# design.net
KiCad netlist of a schematic drawn in EasyEDA Pro
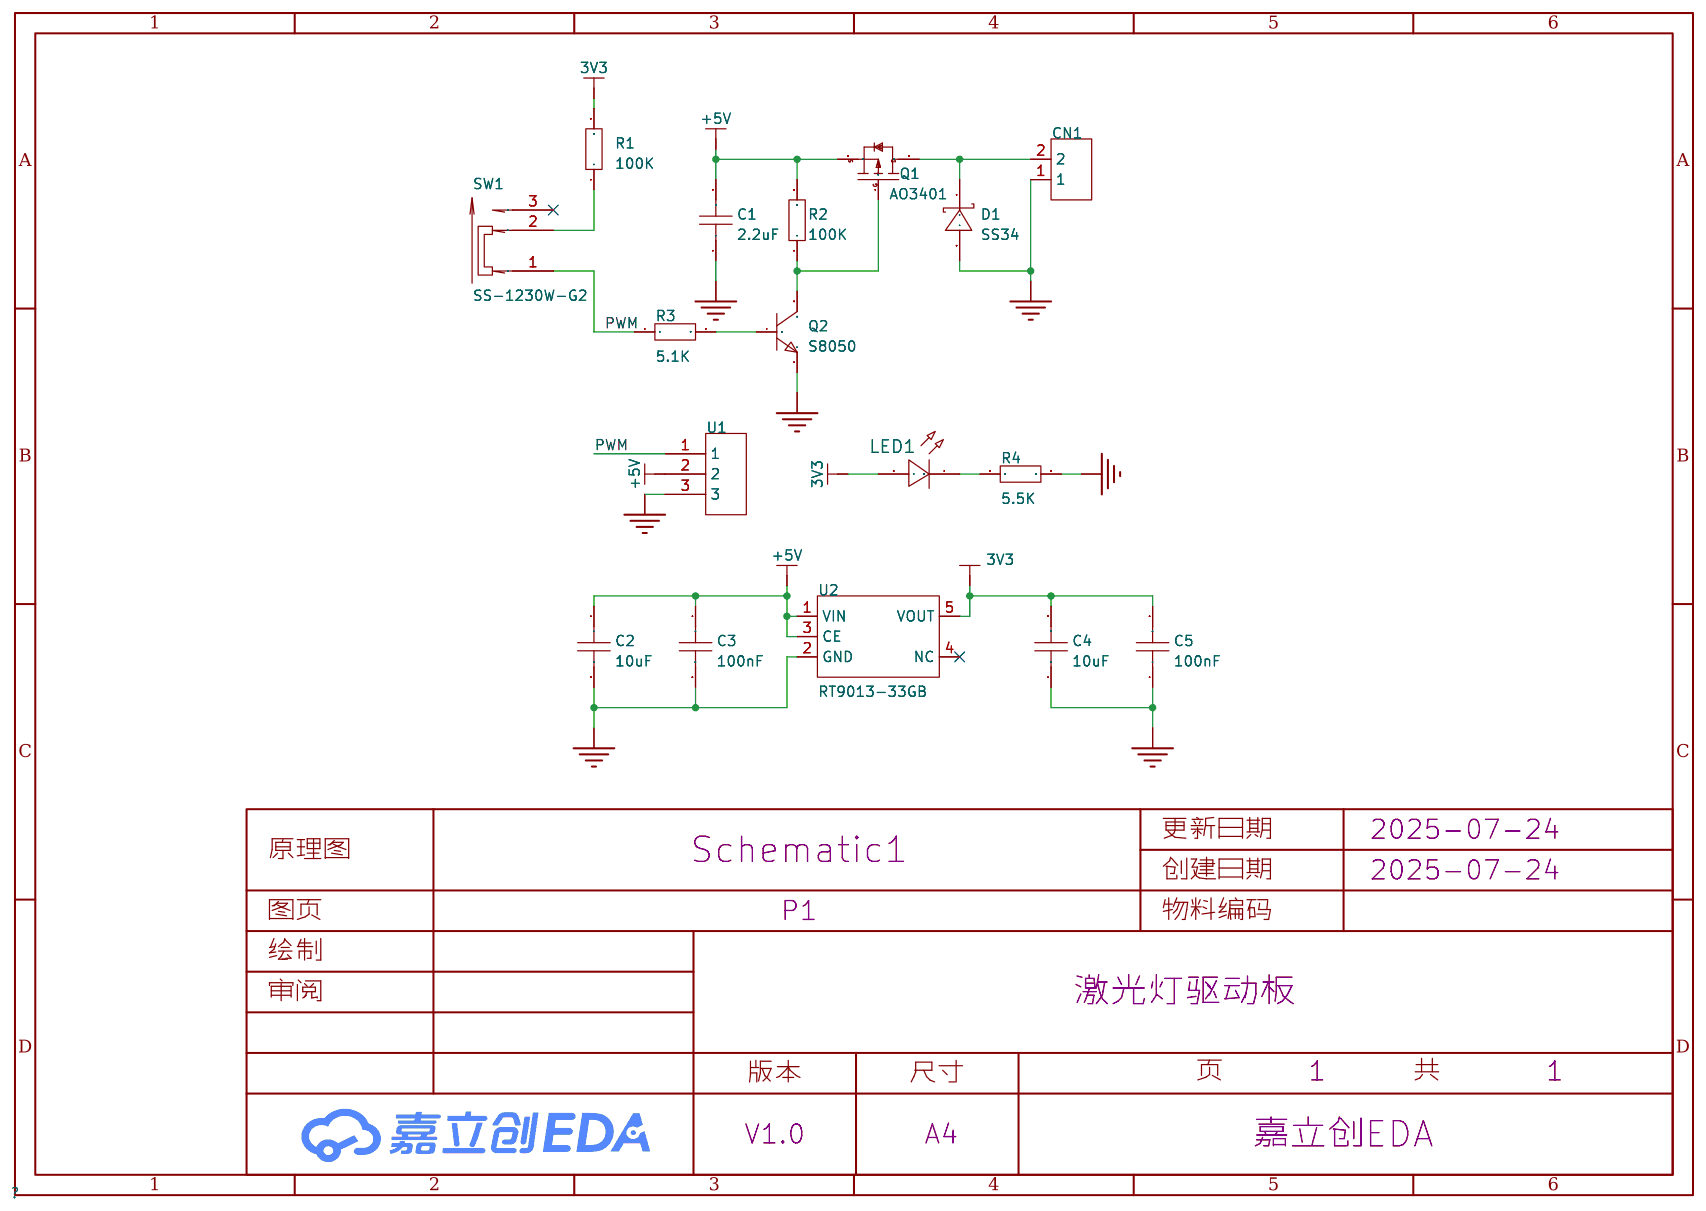
[diagram p0: schematic sheet]

(export (version "E")
  (design (tool "Eeschema 10.0.6"))
  (components
    (comp (ref "C1")
      (value "2.2uF")
      (footprint "easyedapro:C0603")
      (libsource (lib "easyedapro") (part "CapAcitance"))
    )
    (comp (ref "C2")
      (value "10uF")
      (footprint "easyedapro:C0603")
      (libsource (lib "easyedapro") (part "CapAcitance"))
    )
    (comp (ref "C3")
      (value "100nF")
      (footprint "easyedapro:C0603")
      (libsource (lib "easyedapro") (part "CapAcitance"))
    )
    (comp (ref "C4")
      (value "10uF")
      (footprint "easyedapro:C0603")
      (libsource (lib "easyedapro") (part "CapAcitance"))
    )
    (comp (ref "C5")
      (value "100nF")
      (footprint "easyedapro:C0603")
      (libsource (lib "easyedapro") (part "CapAcitance"))
    )
    (comp (ref "CN1")
      (value "XH2.54-2PIN-直针")
      (footprint "easyedapro:CONN-TH_XH2.54-2P")
      (libsource (lib "easyedapro") (part "XH2.54-2PIN-直针"))
    )
    (comp (ref "D1")
      (value "SS34")
      (footprint "easyedapro:SMA_L4.3-W2.6-LS5.0-RD")
      (libsource (lib "easyedapro") (part "SS34_C9900023345"))
    )
    (comp (ref "LED1")
      (value "~")
      (footprint "easyedapro:LED_0603")
      (libsource (lib "easyedapro") (part "LED_R"))
    )
    (comp (ref "Q1")
      (value "AO3401")
      (footprint "easyedapro:SOT-23-3_L2.9-W1.6-P1.90-LS2.8-BR")
      (libsource (lib "easyedapro") (part "AO3401_C9900008520"))
    )
    (comp (ref "Q2")
      (value "S8050")
      (footprint "easyedapro:SOT-23-3_L2.9-W1.3-P1.90-LS2.4-BR")
      (description "NPN 25V 500mA 120-400 SOT-23")
      (fields (field (name "Manufacturer") "Doeshare(德芯)"))
      (libsource (lib "easyedapro") (part "S8050_C2931719"))
    )
    (comp (ref "R1") (value "100K") (footprint "easyedapro:R0603") (libsource (lib "easyedapro") (part "电阻")))
    (comp (ref "R2") (value "100K") (footprint "easyedapro:R0603") (libsource (lib "easyedapro") (part "电阻")))
    (comp (ref "R3") (value "5.1K") (footprint "easyedapro:R0603") (libsource (lib "easyedapro") (part "电阻")))
    (comp (ref "R4") (value "5.5K") (footprint "easyedapro:R0603") (libsource (lib "easyedapro") (part "电阻")))
    (comp (ref "SW1")
      (value "SS-1230W-G2")
      (footprint "easyedapro:SW-SMD_SS-1230W-G2")
      (fields (field (name "Manufacturer") "RISHENG(日昇)"))
      (libsource (lib "easyedapro") (part "SS-1230W-G2"))
    )
    (comp (ref "U1")
      (value "~")
      (footprint "easyedapro:X2.54_3p")
      (libsource (lib "easyedapro") (part "X2.54 _3p"))
    )
    (comp (ref "U2")
      (value "RT9013-33GB")
      (footprint "easyedapro:SOT-23-5_L2.9-W1.6-P0.95-LS2.8-BR")
      (description "输出类型:固定;工作电压:7V;输出电压:3.3V;输出电流:500mA;电源纹波抑制比(PSRR):-;输出极性:正极;")
      (fields (field (name "Manufacturer") "TECH PUBLIC(台舟)"))
      (libsource (lib "easyedapro") (part "RT9013-33GB_C19268157"))
    )
  )
  (nets
    (net (code "1") (name "+5V") (class "Default")
      (node (ref "C1") (pin "2") (pinfunction "2_2") (pintype "input"))
      (node (ref "C2") (pin "1") (pinfunction "1_1") (pintype "input"))
      (node (ref "C3") (pin "1") (pinfunction "1_1") (pintype "input"))
      (node (ref "Q1") (pin "2") (pinfunction "S_2") (pintype "unspecified"))
      (node (ref "R2") (pin "2") (pinfunction "2_2") (pintype "input"))
      (node (ref "U1") (pin "2") (pinfunction "2_2") (pintype "input"))
      (node (ref "U2") (pin "1") (pinfunction "VIN_1") (pintype "unspecified"))
      (node (ref "U2") (pin "3") (pinfunction "CE_3") (pintype "unspecified"))
    )
    (net (code "2") (name "/PWM") (class "Default")
      (node (ref "R3") (pin "1") (pinfunction "1_1") (pintype "input"))
      (node (ref "SW1") (pin "1") (pinfunction "1_1") (pintype "unspecified"))
      (node (ref "U1") (pin "1") (pinfunction "1_1") (pintype "input"))
    )
    (net (code "3") (name "3V3") (class "Default")
      (node (ref "C4") (pin "2") (pinfunction "2_2") (pintype "input"))
      (node (ref "C5") (pin "2") (pinfunction "2_2") (pintype "input"))
      (node (ref "LED1") (pin "2") (pinfunction "A_2") (pintype "input"))
      (node (ref "R1") (pin "2") (pinfunction "2_2") (pintype "input"))
      (node (ref "U2") (pin "5") (pinfunction "VOUT_5") (pintype "unspecified"))
    )
    (net (code "4") (name "GND") (class "Default")
      (node (ref "C1") (pin "1") (pinfunction "1_1") (pintype "input"))
      (node (ref "C2") (pin "2") (pinfunction "2_2") (pintype "input"))
      (node (ref "C3") (pin "2") (pinfunction "2_2") (pintype "input"))
      (node (ref "C4") (pin "1") (pinfunction "1_1") (pintype "input"))
      (node (ref "C5") (pin "1") (pinfunction "1_1") (pintype "input"))
      (node (ref "CN1") (pin "1") (pinfunction "1_1") (pintype "unspecified"))
      (node (ref "D1") (pin "2") (pinfunction "A_2") (pintype "unspecified"))
      (node (ref "Q2") (pin "2") (pinfunction "E_2") (pintype "input"))
      (node (ref "R4") (pin "2") (pinfunction "2_2") (pintype "input"))
      (node (ref "U1") (pin "3") (pinfunction "3_3") (pintype "input"))
      (node (ref "U2") (pin "2") (pinfunction "GND_2") (pintype "unspecified"))
    )
    (net (code "5") (name "Net-(D1-K)") (class "Default")
      (node (ref "CN1") (pin "2") (pinfunction "2_2") (pintype "unspecified"))
      (node (ref "D1") (pin "1") (pinfunction "K_1") (pintype "unspecified"))
      (node (ref "Q1") (pin "3") (pinfunction "D_3") (pintype "unspecified"))
    )
    (net (code "6") (name "Net-(LED1-C)") (class "Default")
      (node (ref "LED1") (pin "1") (pinfunction "C_1") (pintype "input"))
      (node (ref "R4") (pin "1") (pinfunction "1_1") (pintype "input"))
    )
    (net (code "7") (name "Net-(Q1-G)") (class "Default")
      (node (ref "Q1") (pin "1") (pinfunction "G_1") (pintype "unspecified"))
      (node (ref "Q2") (pin "3") (pinfunction "C_3") (pintype "input"))
      (node (ref "R2") (pin "1") (pinfunction "1_1") (pintype "input"))
    )
    (net (code "8") (name "Net-(Q2-B)") (class "Default")
      (node (ref "Q2") (pin "1") (pinfunction "B_1") (pintype "input"))
      (node (ref "R3") (pin "2") (pinfunction "2_2") (pintype "input"))
    )
    (net (code "9") (name "Net-(R1-Pad1)") (class "Default")
      (node (ref "R1") (pin "1") (pinfunction "1_1") (pintype "input"))
      (node (ref "SW1") (pin "2") (pinfunction "2_2") (pintype "unspecified"))
    )
    (net (code "10") (name "unconnected-(SW1-Pad3)") (class "Default")
      (node (ref "SW1") (pin "3") (pinfunction "3_3") (pintype "unspecified+no_connect"))
    )
    (net (code "11") (name "unconnected-(U2-NC-Pad4)") (class "Default")
      (node (ref "U2") (pin "4") (pinfunction "NC_4") (pintype "unspecified+no_connect"))
    )
  )
)
